# BT832A.net
KiCad netlist of a schematic drawn in EAGLE
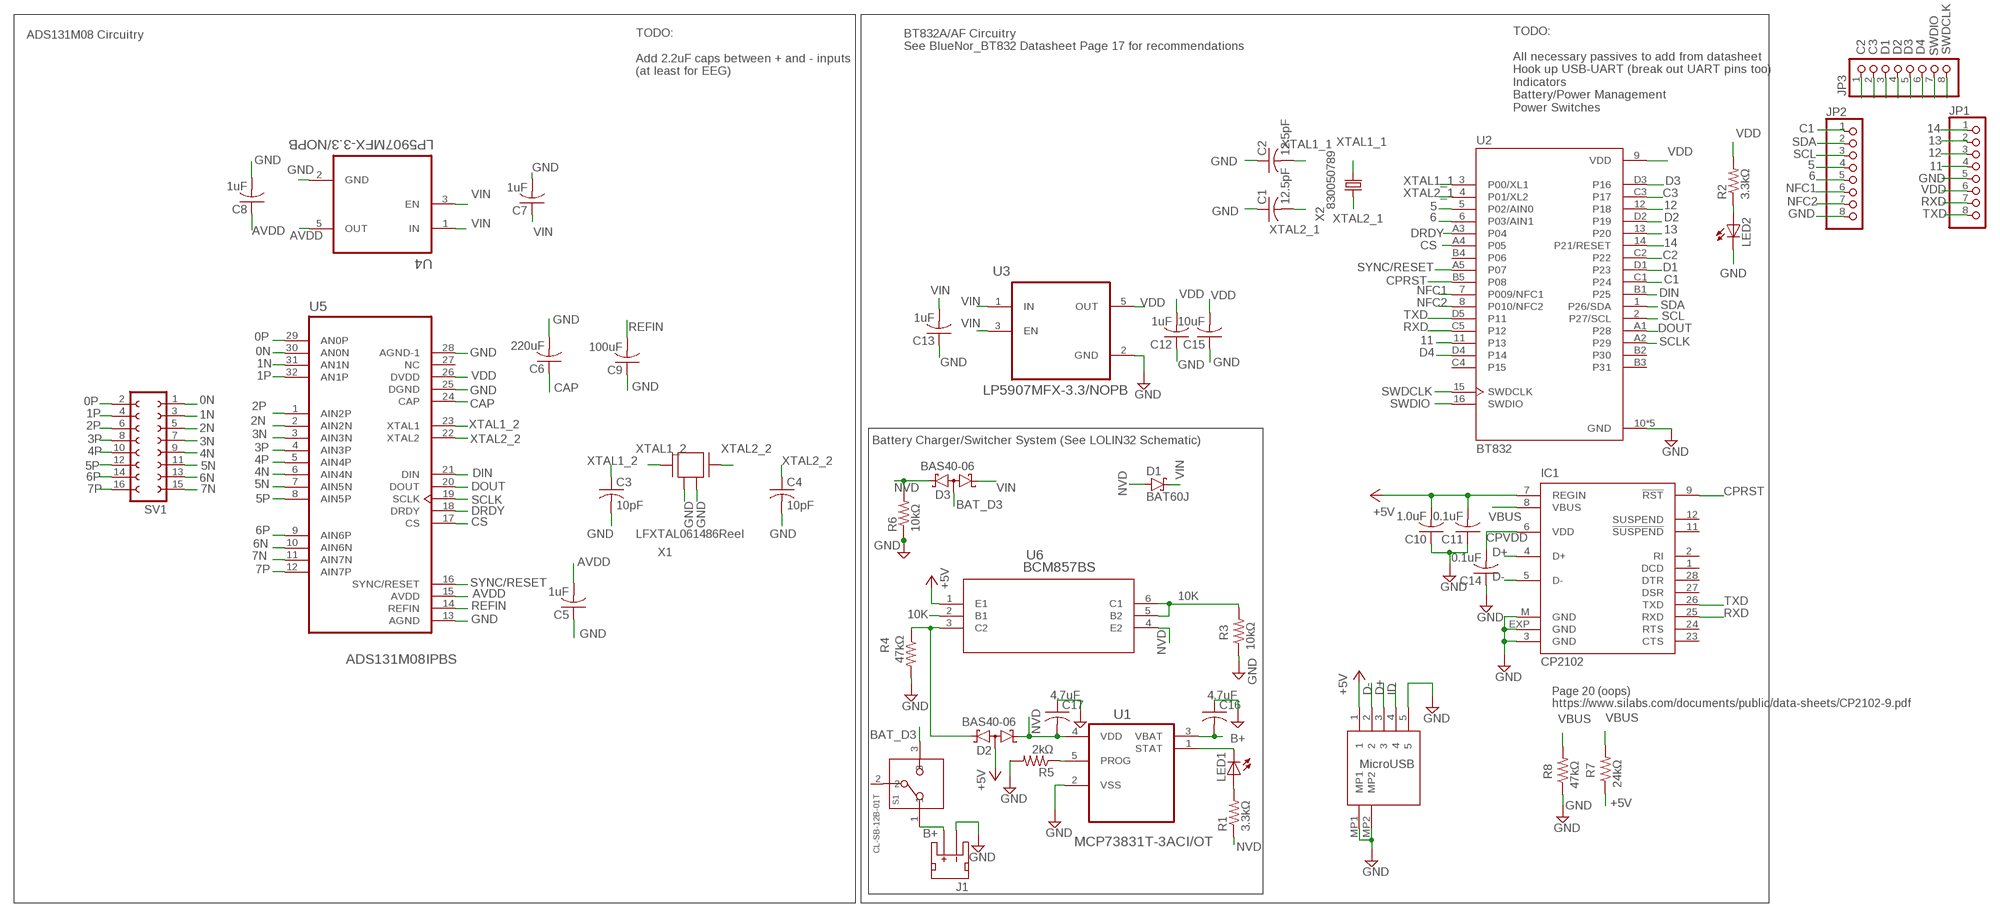
[diagram p0: schematic, sheet 1]

(export (version "E")
  (design (tool "Eeschema 10.0.6"))
  (components
    (comp (ref "C1")
      (value "12.5pF")
      (footprint "eagle-import:C0402")
      (libsource (lib "eagle-import") (part "adafruit_420_C-USC0402"))
    )
    (comp (ref "C2")
      (value "12.5pF")
      (footprint "eagle-import:C0402")
      (libsource (lib "eagle-import") (part "adafruit_420_C-USC0402"))
    )
    (comp (ref "C3")
      (value "10pF")
      (footprint "eagle-import:C0402")
      (libsource (lib "eagle-import") (part "adafruit_420_C-USC0402"))
    )
    (comp (ref "C4")
      (value "10pF")
      (footprint "eagle-import:C0402")
      (libsource (lib "eagle-import") (part "adafruit_420_C-USC0402"))
    )
    (comp (ref "C5")
      (value "1uF")
      (footprint "eagle-import:C0402")
      (libsource (lib "eagle-import") (part "C-USC0402"))
    )
    (comp (ref "C6")
      (value "220uF")
      (footprint "eagle-import:C0402")
      (libsource (lib "eagle-import") (part "C-USC0402"))
    )
    (comp (ref "C7")
      (value "1uF")
      (footprint "eagle-import:C0402")
      (libsource (lib "eagle-import") (part "C-USC0402"))
    )
    (comp (ref "C8")
      (value "1uF")
      (footprint "eagle-import:C0402")
      (libsource (lib "eagle-import") (part "C-USC0402"))
    )
    (comp (ref "C9")
      (value "100uF")
      (footprint "eagle-import:C0402")
      (libsource (lib "eagle-import") (part "C-USC0402"))
    )
    (comp (ref "C10")
      (value "1.0uF")
      (footprint "eagle-import:C0402")
      (libsource (lib "eagle-import") (part "adafruit_420_C-USC0402"))
    )
    (comp (ref "C11")
      (value "0.1uF")
      (footprint "eagle-import:C0402")
      (libsource (lib "eagle-import") (part "adafruit_420_C-USC0402"))
    )
    (comp (ref "C12")
      (value "1uF")
      (footprint "eagle-import:C0402")
      (libsource (lib "eagle-import") (part "C-USC0402"))
    )
    (comp (ref "C13")
      (value "1uF")
      (footprint "eagle-import:C0402")
      (libsource (lib "eagle-import") (part "C-USC0402"))
    )
    (comp (ref "C14")
      (value "0.1uF")
      (footprint "eagle-import:C0402")
      (libsource (lib "eagle-import") (part "adafruit_420_C-USC0402"))
    )
    (comp (ref "C15")
      (value "10uF")
      (footprint "eagle-import:C0402")
      (libsource (lib "eagle-import") (part "C-USC0402"))
    )
    (comp (ref "C16")
      (value "4.7uF")
      (footprint "eagle-import:C0402")
      (libsource (lib "eagle-import") (part "adafruit_420_C-USC0402"))
    )
    (comp (ref "C17")
      (value "4.7uF")
      (footprint "eagle-import:C0402")
      (libsource (lib "eagle-import") (part "adafruit_420_C-USC0402"))
    )
    (comp (ref "D1")
      (value "BAT60J")
      (footprint "eagle-import:SOD323_ST")
      (libsource (lib "eagle-import") (part "BAT60J"))
    )
    (comp (ref "D2")
      (value "BAS40-06")
      (footprint "eagle-import:SOT23")
      (libsource (lib "eagle-import") (part "BAS40-06"))
    )
    (comp (ref "D3")
      (value "BAS40-06")
      (footprint "eagle-import:SOT23")
      (libsource (lib "eagle-import") (part "BAS40-06"))
    )
    (comp (ref "IC1")
      (value "CP2102")
      (footprint "eagle-import:MLP28")
      (fields (field (name "MF") "FARNELL") (field (name "MPN") "CP2102-GM"))
      (libsource (lib "eagle-import") (part "CP2102"))
    )
    (comp (ref "J1")
      (value "JST_2MM_MALE")
      (footprint "eagle-import:JST-2-SMD")
      (libsource (lib "eagle-import") (part "JST_2MM_MALE"))
    )
    (comp (ref "JP1")
      (value "PINHD-1X8CLEANBIG")
      (footprint "eagle-import:1X08-CLEANBIG")
      (libsource (lib "eagle-import") (part "PINHD-1X8CLEANBIG"))
    )
    (comp (ref "JP2")
      (value "PINHD-1X8CLEANBIG")
      (footprint "eagle-import:1X08-CLEANBIG")
      (libsource (lib "eagle-import") (part "PINHD-1X8CLEANBIG"))
    )
    (comp (ref "JP3")
      (value "PINHD-1X8CLEANBIG")
      (footprint "eagle-import:1X08-CLEANBIG")
      (libsource (lib "eagle-import") (part "PINHD-1X8CLEANBIG"))
    )
    (comp (ref "LED1")
      (value "LEDCHIP-LED0603")
      (footprint "eagle-import:CHIP-LED0603")
      (libsource (lib "eagle-import") (part "LEDCHIP-LED0603"))
    )
    (comp (ref "LED2")
      (value "LEDCHIP-LED0603")
      (footprint "eagle-import:CHIP-LED0603")
      (libsource (lib "eagle-import") (part "LEDCHIP-LED0603"))
    )
    (comp (ref "R1")
      (value "3.3kΩ")
      (footprint "eagle-import:R0402")
      (libsource (lib "eagle-import") (part "R-US_R0402"))
    )
    (comp (ref "R2")
      (value "3.3kΩ")
      (footprint "eagle-import:R0402")
      (libsource (lib "eagle-import") (part "R-US_R0402"))
    )
    (comp (ref "R3")
      (value "10kΩ")
      (footprint "eagle-import:R0402")
      (libsource (lib "eagle-import") (part "R-US_R0402"))
    )
    (comp (ref "R4")
      (value "47kΩ")
      (footprint "eagle-import:R0402")
      (libsource (lib "eagle-import") (part "R-US_R0402"))
    )
    (comp (ref "R5")
      (value "2kΩ")
      (footprint "eagle-import:R0402")
      (libsource (lib "eagle-import") (part "R-US_R0402"))
    )
    (comp (ref "R6")
      (value "10kΩ")
      (footprint "eagle-import:R0402")
      (libsource (lib "eagle-import") (part "R-US_R0402"))
    )
    (comp (ref "R7")
      (value "24kΩ")
      (footprint "eagle-import:R0402")
      (libsource (lib "eagle-import") (part "R-US_R0402"))
    )
    (comp (ref "R8")
      (value "47kΩ")
      (footprint "eagle-import:R0402")
      (libsource (lib "eagle-import") (part "R-US_R0402"))
    )
    (comp (ref "S1")
      (value "CL-SB-12B-01T")
      (footprint "eagle-import:CL-SB-12B")
      (fields (field (name "MF") "Nidec Copal"))
      (libsource (lib "eagle-import") (part "CL-SB-12B-01T"))
    )
    (comp (ref "SV1")
      (value "FE08-2")
      (footprint "eagle-import:FE08-2")
      (libsource (lib "eagle-import") (part "FE08-2"))
    )
    (comp (ref "U$1")
      (value "DX4R005JJ2R1800")
      (footprint "eagle-import:DX4R005JJ2R1800")
      (fields (field (name "MF") "JAE Electronics"))
      (libsource (lib "eagle-import") (part "DX4R005JJ2R1800"))
    )
    (comp (ref "U1")
      (value "MCP73831T-3ACI/OT")
      (footprint "eagle-import:SOT95P270X145-5N")
      (fields (field (name "MF") "Microchip"))
      (libsource (lib "eagle-import") (part "MCP73831T-3ACI/OT"))
    )
    (comp (ref "U2")
      (value "BT832")
      (footprint "eagle-import:BLEMODULE_BT832")
      (fields (field (name "MF") "Fanstel Corp."))
      (libsource (lib "eagle-import") (part "BT832"))
    )
    (comp (ref "U3")
      (value "LP5907MFX-3.3/NOPB")
      (footprint "eagle-import:SOT95P280X145-5N")
      (fields (field (name "MF") "Texas Instruments"))
      (libsource (lib "eagle-import") (part "LP5907MFX-3.3/NOPB"))
    )
    (comp (ref "U4")
      (value "LP5907MFX-3.3/NOPB")
      (footprint "eagle-import:SOT95P280X145-5N")
      (fields (field (name "MF") "Texas Instruments"))
      (libsource (lib "eagle-import") (part "LP5907MFX-3.3/NOPB"))
    )
    (comp (ref "U5")
      (value "ADS131M08IPBS")
      (footprint "eagle-import:QFP50P700X700X120-32N")
      (fields (field (name "MF") "Texas Instruments"))
      (libsource (lib "eagle-import") (part "ADS131M08IPBS"))
    )
    (comp (ref "U6")
      (value "BCM857BS")
      (footprint "eagle-import:SOT363_NEX")
      (fields (field (name "COPYRIGHT") "Copyright (C) 2016 Accelerated Designs. All rights reserved"))
      (libsource (lib "eagle-import") (part "BCM857BS"))
    )
    (comp (ref "X1")
      (value "ABM3B-8.000MHZ-B2-T")
      (footprint "eagle-import:ABM3B-8.000MHZ-B2-T")
      (fields
        (field (name "DIGIKEY_PART_NUMBER") "535-9720-2-ND")
        (field (name "MANUFACTURER") "Abracon LLC")
        (field (name "CREATED_BY") "PCBLayout.com")
      )
      (libsource (lib "eagle-import") (part "ABM3B-8.000MHZ-B2-T"))
    )
    (comp (ref "X2")
      (value "FC-12M")
      (footprint "eagle-import:FC-12M")
      (libsource (lib "eagle-import") (part "FC-12M"))
    )
  )
  (nets
    (net (code "1") (name "+5V") (class "Default")
      (node (ref "C10") (pin "2") (pinfunction "2_2") (pintype "passive"))
      (node (ref "C11") (pin "2") (pinfunction "2_2") (pintype "passive"))
      (node (ref "D2") (pin "3") (pinfunction "AA_3") (pintype "passive"))
      (node (ref "IC1") (pin "7") (pinfunction "REGIN_7") (pintype "passive"))
      (node (ref "R7") (pin "1") (pinfunction "1_1") (pintype "passive"))
      (node (ref "U$1") (pin "1") (pinfunction "1_1") (pintype "bidirectional"))
      (node (ref "U6") (pin "1") (pinfunction "E1_1") (pintype "passive"))
    )
    (net (code "2") (name "0N") (class "Default")
      (node (ref "SV1") (pin "1") (pinfunction "1_1") (pintype "passive"))
      (node (ref "U5") (pin "30") (pinfunction "AN0N_30") (pintype "bidirectional"))
    )
    (net (code "3") (name "0P") (class "Default")
      (node (ref "SV1") (pin "2") (pinfunction "2_2") (pintype "passive"))
      (node (ref "U5") (pin "29") (pinfunction "AN0P_29") (pintype "bidirectional"))
    )
    (net (code "4") (name "1N") (class "Default")
      (node (ref "SV1") (pin "3") (pinfunction "3_3") (pintype "passive"))
      (node (ref "U5") (pin "31") (pinfunction "AN1N_31") (pintype "bidirectional"))
    )
    (net (code "5") (name "1P") (class "Default")
      (node (ref "SV1") (pin "4") (pinfunction "4_4") (pintype "passive"))
      (node (ref "U5") (pin "32") (pinfunction "AN1P_32") (pintype "bidirectional"))
    )
    (net (code "6") (name "2N") (class "Default")
      (node (ref "SV1") (pin "5") (pinfunction "5_5") (pintype "passive"))
      (node (ref "U5") (pin "2") (pinfunction "AIN2N_2") (pintype "input"))
    )
    (net (code "7") (name "2P") (class "Default")
      (node (ref "SV1") (pin "6") (pinfunction "6_6") (pintype "passive"))
      (node (ref "U5") (pin "1") (pinfunction "AIN2P_1") (pintype "input"))
    )
    (net (code "8") (name "3N") (class "Default")
      (node (ref "SV1") (pin "7") (pinfunction "7_7") (pintype "passive"))
      (node (ref "U5") (pin "3") (pinfunction "AIN3N_3") (pintype "input"))
    )
    (net (code "9") (name "3P") (class "Default")
      (node (ref "SV1") (pin "8") (pinfunction "8_8") (pintype "passive"))
      (node (ref "U5") (pin "4") (pinfunction "AIN3P_4") (pintype "input"))
    )
    (net (code "10") (name "4N") (class "Default")
      (node (ref "SV1") (pin "9") (pinfunction "9_9") (pintype "passive"))
      (node (ref "U5") (pin "6") (pinfunction "AIN4N_6") (pintype "input"))
    )
    (net (code "11") (name "4P") (class "Default")
      (node (ref "SV1") (pin "10") (pinfunction "10_10") (pintype "passive"))
      (node (ref "U5") (pin "5") (pinfunction "AIN4P_5") (pintype "input"))
    )
    (net (code "12") (name "5") (class "Default")
      (node (ref "JP2") (pin "4") (pinfunction "4_4") (pintype "passive"))
      (node (ref "U2") (pin "5") (pinfunction "P02/AIN0_5") (pintype "bidirectional"))
    )
    (net (code "13") (name "5N") (class "Default")
      (node (ref "SV1") (pin "11") (pinfunction "11_11") (pintype "passive"))
      (node (ref "U5") (pin "7") (pinfunction "AIN5N_7") (pintype "input"))
    )
    (net (code "14") (name "5P") (class "Default")
      (node (ref "SV1") (pin "12") (pinfunction "12_12") (pintype "passive"))
      (node (ref "U5") (pin "8") (pinfunction "AIN5P_8") (pintype "input"))
    )
    (net (code "15") (name "6") (class "Default")
      (node (ref "JP2") (pin "5") (pinfunction "5_5") (pintype "passive"))
      (node (ref "U2") (pin "6") (pinfunction "P03/AIN1_6") (pintype "bidirectional"))
    )
    (net (code "16") (name "6N") (class "Default")
      (node (ref "SV1") (pin "13") (pinfunction "13_13") (pintype "passive"))
      (node (ref "U5") (pin "10") (pinfunction "AIN6N_10") (pintype "input"))
    )
    (net (code "17") (name "6P") (class "Default")
      (node (ref "SV1") (pin "14") (pinfunction "14_14") (pintype "passive"))
      (node (ref "U5") (pin "9") (pinfunction "AIN6P_9") (pintype "input"))
    )
    (net (code "18") (name "7N") (class "Default")
      (node (ref "SV1") (pin "15") (pinfunction "15_15") (pintype "passive"))
      (node (ref "U5") (pin "11") (pinfunction "AIN7N_11") (pintype "input"))
    )
    (net (code "19") (name "7P") (class "Default")
      (node (ref "SV1") (pin "16") (pinfunction "16_16") (pintype "passive"))
      (node (ref "U5") (pin "12") (pinfunction "AIN7P_12") (pintype "input"))
    )
    (net (code "20") (name "10K") (class "Default")
      (node (ref "R3") (pin "2") (pinfunction "2_2") (pintype "passive"))
      (node (ref "U6") (pin "2") (pinfunction "B1_2") (pintype "passive"))
      (node (ref "U6") (pin "5") (pinfunction "B2_5") (pintype "passive"))
      (node (ref "U6") (pin "6") (pinfunction "C1_6") (pintype "passive"))
    )
    (net (code "21") (name "11") (class "Default")
      (node (ref "JP1") (pin "4") (pinfunction "4_4") (pintype "passive"))
      (node (ref "U2") (pin "11") (pinfunction "P13_11") (pintype "bidirectional"))
    )
    (net (code "22") (name "12") (class "Default")
      (node (ref "JP1") (pin "3") (pinfunction "3_3") (pintype "passive"))
      (node (ref "U2") (pin "12") (pinfunction "P18_12") (pintype "bidirectional"))
    )
    (net (code "23") (name "13") (class "Default")
      (node (ref "JP1") (pin "2") (pinfunction "2_2") (pintype "passive"))
      (node (ref "U2") (pin "13") (pinfunction "P20_13") (pintype "bidirectional"))
    )
    (net (code "24") (name "14") (class "Default")
      (node (ref "JP1") (pin "1") (pinfunction "1_1") (pintype "passive"))
      (node (ref "U2") (pin "14") (pinfunction "P21/RESET_14") (pintype "bidirectional"))
    )
    (net (code "25") (name "AVDD") (class "Default")
      (node (ref "C5") (pin "2") (pinfunction "2_2") (pintype "passive"))
      (node (ref "C8") (pin "1") (pinfunction "1_1") (pintype "passive"))
      (node (ref "U4") (pin "5") (pinfunction "OUT_5") (pintype "output"))
      (node (ref "U5") (pin "15") (pinfunction "AVDD_15") (pintype "power_in"))
    )
    (net (code "26") (name "B+") (class "Default")
      (node (ref "C16") (pin "2") (pinfunction "2_2") (pintype "passive"))
      (node (ref "J1") (pin "2") (pinfunction "+_2") (pintype "bidirectional"))
      (node (ref "S1") (pin "1") (pinfunction "1_1") (pintype "bidirectional"))
      (node (ref "U1") (pin "3") (pinfunction "VBAT_3") (pintype "power_in"))
    )
    (net (code "27") (name "BAT_D3") (class "Default")
      (node (ref "D3") (pin "3") (pinfunction "AA_3") (pintype "passive"))
      (node (ref "S1") (pin "3") (pinfunction "3_3") (pintype "bidirectional"))
    )
    (net (code "28") (name "C1") (class "Default")
      (node (ref "JP2") (pin "1") (pinfunction "1_1") (pintype "passive"))
      (node (ref "U2") (pin "C1") (pinfunction "P24_C1") (pintype "bidirectional"))
    )
    (net (code "29") (name "C2") (class "Default")
      (node (ref "JP3") (pin "1") (pinfunction "1_1") (pintype "passive"))
      (node (ref "U2") (pin "C2") (pinfunction "P22_C2") (pintype "bidirectional"))
    )
    (net (code "30") (name "C3") (class "Default")
      (node (ref "JP3") (pin "2") (pinfunction "2_2") (pintype "passive"))
      (node (ref "U2") (pin "C3") (pinfunction "P17_C3") (pintype "bidirectional"))
    )
    (net (code "31") (name "CAP") (class "Default")
      (node (ref "C6") (pin "1") (pinfunction "1_1") (pintype "passive"))
      (node (ref "U5") (pin "24") (pinfunction "CAP_24") (pintype "bidirectional"))
    )
    (net (code "32") (name "CPRST") (class "Default")
      (node (ref "IC1") (pin "9") (pinfunction "~{RST}_9") (pintype "bidirectional"))
      (node (ref "U2") (pin "B5") (pinfunction "P08_B5") (pintype "bidirectional"))
    )
    (net (code "33") (name "CPVDD") (class "Default")
      (node (ref "C14") (pin "2") (pinfunction "2_2") (pintype "passive"))
      (node (ref "IC1") (pin "6") (pinfunction "VDD_6") (pintype "power_in"))
    )
    (net (code "34") (name "CS") (class "Default")
      (node (ref "U2") (pin "A4") (pinfunction "P05_A4") (pintype "bidirectional"))
      (node (ref "U5") (pin "17") (pinfunction "CS_17") (pintype "bidirectional"))
    )
    (net (code "35") (name "D+") (class "Default")
      (node (ref "IC1") (pin "4") (pinfunction "D+_4") (pintype "bidirectional"))
      (node (ref "U$1") (pin "3") (pinfunction "3_3") (pintype "bidirectional"))
    )
    (net (code "36") (name "D-") (class "Default")
      (node (ref "IC1") (pin "5") (pinfunction "D-_5") (pintype "bidirectional"))
      (node (ref "U$1") (pin "2") (pinfunction "2_2") (pintype "bidirectional"))
    )
    (net (code "37") (name "D1") (class "Default")
      (node (ref "JP3") (pin "3") (pinfunction "3_3") (pintype "passive"))
      (node (ref "U2") (pin "D1") (pinfunction "P23_D1") (pintype "bidirectional"))
    )
    (net (code "38") (name "D2") (class "Default")
      (node (ref "JP3") (pin "4") (pinfunction "4_4") (pintype "passive"))
      (node (ref "U2") (pin "D2") (pinfunction "P19_D2") (pintype "bidirectional"))
    )
    (net (code "39") (name "D3") (class "Default")
      (node (ref "JP3") (pin "5") (pinfunction "5_5") (pintype "passive"))
      (node (ref "U2") (pin "D3") (pinfunction "P16_D3") (pintype "bidirectional"))
    )
    (net (code "40") (name "D4") (class "Default")
      (node (ref "JP3") (pin "6") (pinfunction "6_6") (pintype "passive"))
      (node (ref "U2") (pin "D4") (pinfunction "P14_D4") (pintype "bidirectional"))
    )
    (net (code "41") (name "DIN") (class "Default")
      (node (ref "U2") (pin "B1") (pinfunction "P25_B1") (pintype "bidirectional"))
      (node (ref "U5") (pin "21") (pinfunction "DIN_21") (pintype "input"))
    )
    (net (code "42") (name "DOUT") (class "Default")
      (node (ref "U2") (pin "A1") (pinfunction "P28_A1") (pintype "bidirectional"))
      (node (ref "U5") (pin "20") (pinfunction "DOUT_20") (pintype "output"))
    )
    (net (code "43") (name "DRDY") (class "Default")
      (node (ref "U2") (pin "A3") (pinfunction "P04_A3") (pintype "bidirectional"))
      (node (ref "U5") (pin "18") (pinfunction "DRDY_18") (pintype "output"))
    )
    (net (code "44") (name "GND") (class "Default")
      (node (ref "C1") (pin "1") (pinfunction "1_1") (pintype "passive"))
      (node (ref "C10") (pin "1") (pinfunction "1_1") (pintype "passive"))
      (node (ref "C11") (pin "1") (pinfunction "1_1") (pintype "passive"))
      (node (ref "C12") (pin "1") (pinfunction "1_1") (pintype "passive"))
      (node (ref "C13") (pin "1") (pinfunction "1_1") (pintype "passive"))
      (node (ref "C14") (pin "1") (pinfunction "1_1") (pintype "passive"))
      (node (ref "C15") (pin "1") (pinfunction "1_1") (pintype "passive"))
      (node (ref "C16") (pin "1") (pinfunction "1_1") (pintype "passive"))
      (node (ref "C17") (pin "1") (pinfunction "1_1") (pintype "passive"))
      (node (ref "C2") (pin "1") (pinfunction "1_1") (pintype "passive"))
      (node (ref "C3") (pin "2") (pinfunction "2_2") (pintype "passive"))
      (node (ref "C4") (pin "2") (pinfunction "2_2") (pintype "passive"))
      (node (ref "C5") (pin "1") (pinfunction "1_1") (pintype "passive"))
      (node (ref "C6") (pin "2") (pinfunction "2_2") (pintype "passive"))
      (node (ref "C7") (pin "2") (pinfunction "2_2") (pintype "passive"))
      (node (ref "C8") (pin "2") (pinfunction "2_2") (pintype "passive"))
      (node (ref "C9") (pin "1") (pinfunction "1_1") (pintype "passive"))
      (node (ref "IC1") (pin "3") (pinfunction "GND_3") (pintype "power_in"))
      (node (ref "IC1") (pin "EXP") (pinfunction "GND_EXP") (pintype "power_in"))
      (node (ref "IC1") (pin "M") (pinfunction "GND_M") (pintype "power_in"))
      (node (ref "J1") (pin "1") (pinfunction "-_1") (pintype "bidirectional"))
      (node (ref "JP1") (pin "5") (pinfunction "5_5") (pintype "passive"))
      (node (ref "JP2") (pin "8") (pinfunction "8_8") (pintype "passive"))
      (node (ref "LED2") (pin "C") (pinfunction "C_C") (pintype "passive"))
      (node (ref "R3") (pin "1") (pinfunction "1_1") (pintype "passive"))
      (node (ref "R4") (pin "2") (pinfunction "2_2") (pintype "passive"))
      (node (ref "R5") (pin "2") (pinfunction "2_2") (pintype "passive"))
      (node (ref "R6") (pin "1") (pinfunction "1_1") (pintype "passive"))
      (node (ref "R8") (pin "1") (pinfunction "1_1") (pintype "passive"))
      (node (ref "U$1") (pin "5") (pinfunction "5_5") (pintype "bidirectional"))
      (node (ref "U$1") (pin "MP1") (pinfunction "MP1_MP1") (pintype "bidirectional"))
      (node (ref "U$1") (pin "MP2") (pinfunction "MP2_MP2") (pintype "bidirectional"))
      (node (ref "U1") (pin "2") (pinfunction "VSS_2") (pintype "power_in"))
      (node (ref "U2") (pin "10") (pinfunction "GND_10") (pintype "power_in"))
      (node (ref "U2") (pin "A0") (pinfunction "GND_A0") (pintype "power_in"))
      (node (ref "U2") (pin "B0") (pinfunction "GND_B0") (pintype "power_in"))
      (node (ref "U2") (pin "C0") (pinfunction "GND_C0") (pintype "power_in"))
      (node (ref "U2") (pin "D0") (pinfunction "GND_D0") (pintype "power_in"))
      (node (ref "U3") (pin "2") (pinfunction "GND_2") (pintype "power_in"))
      (node (ref "U4") (pin "2") (pinfunction "GND_2") (pintype "power_in"))
      (node (ref "U5") (pin "13") (pinfunction "AGND_13") (pintype "power_in"))
      (node (ref "U5") (pin "25") (pinfunction "DGND_25") (pintype "power_in"))
      (node (ref "U5") (pin "28") (pinfunction "AGND-1_28") (pintype "power_in"))
      (node (ref "X1") (pin "2") (pinfunction "2_2") (pintype "passive"))
      (node (ref "X1") (pin "4") (pinfunction "4_4") (pintype "passive"))
    )
    (net (code "45") (name "ID") (class "Default")
      (node (ref "U$1") (pin "4") (pinfunction "4_4") (pintype "bidirectional"))
    )
    (net (code "46") (name "NFC1") (class "Default")
      (node (ref "JP2") (pin "6") (pinfunction "6_6") (pintype "passive"))
      (node (ref "U2") (pin "7") (pinfunction "P009/NFC1_7") (pintype "bidirectional"))
    )
    (net (code "47") (name "NFC2") (class "Default")
      (node (ref "JP2") (pin "7") (pinfunction "7_7") (pintype "passive"))
      (node (ref "U2") (pin "8") (pinfunction "P010/NFC2_8") (pintype "bidirectional"))
    )
    (net (code "48") (name "NVD") (class "Default")
      (node (ref "C17") (pin "2") (pinfunction "2_2") (pintype "passive"))
      (node (ref "D1") (pin "A") (pinfunction "A_A") (pintype "passive"))
      (node (ref "D2") (pin "1") (pinfunction "K1_1") (pintype "passive"))
      (node (ref "D3") (pin "2") (pinfunction "K2_2") (pintype "passive"))
      (node (ref "R1") (pin "1") (pinfunction "1_1") (pintype "passive"))
      (node (ref "R6") (pin "2") (pinfunction "2_2") (pintype "passive"))
      (node (ref "U1") (pin "4") (pinfunction "VDD_4") (pintype "power_in"))
      (node (ref "U6") (pin "4") (pinfunction "E2_4") (pintype "passive"))
    )
    (net (code "49") (name "Net-(D2-K2)") (class "Default")
      (node (ref "D2") (pin "2") (pinfunction "K2_2") (pintype "passive"))
      (node (ref "R4") (pin "1") (pinfunction "1_1") (pintype "passive"))
      (node (ref "U6") (pin "3") (pinfunction "C2_3") (pintype "passive"))
    )
    (net (code "50") (name "Net-(LED1-PadA)") (class "Default")
      (node (ref "LED1") (pin "A") (pinfunction "A_A") (pintype "passive"))
      (node (ref "R1") (pin "2") (pinfunction "2_2") (pintype "passive"))
    )
    (net (code "51") (name "Net-(LED2-PadA)") (class "Default")
      (node (ref "LED2") (pin "A") (pinfunction "A_A") (pintype "passive"))
      (node (ref "R2") (pin "1") (pinfunction "1_1") (pintype "passive"))
    )
    (net (code "52") (name "Net-(U1-PROG)") (class "Default")
      (node (ref "R5") (pin "1") (pinfunction "1_1") (pintype "passive"))
      (node (ref "U1") (pin "5") (pinfunction "PROG_5") (pintype "input"))
    )
    (net (code "53") (name "Net-(U1-STAT)") (class "Default")
      (node (ref "LED1") (pin "C") (pinfunction "C_C") (pintype "passive"))
      (node (ref "U1") (pin "1") (pinfunction "STAT_1") (pintype "output"))
    )
    (net (code "54") (name "REFIN") (class "Default")
      (node (ref "C9") (pin "2") (pinfunction "2_2") (pintype "passive"))
      (node (ref "U5") (pin "14") (pinfunction "REFIN_14") (pintype "input"))
    )
    (net (code "55") (name "RXD") (class "Default")
      (node (ref "IC1") (pin "25") (pinfunction "RXD_25") (pintype "input"))
      (node (ref "JP1") (pin "7") (pinfunction "7_7") (pintype "passive"))
      (node (ref "U2") (pin "C5") (pinfunction "P12_C5") (pintype "bidirectional"))
    )
    (net (code "56") (name "SCL") (class "Default")
      (node (ref "JP2") (pin "3") (pinfunction "3_3") (pintype "passive"))
      (node (ref "U2") (pin "2") (pinfunction "P27/SCL_2") (pintype "bidirectional"))
    )
    (net (code "57") (name "SCLK") (class "Default")
      (node (ref "U2") (pin "A2") (pinfunction "P29_A2") (pintype "bidirectional"))
      (node (ref "U5") (pin "19") (pinfunction "SCLK_19") (pintype "input"))
    )
    (net (code "58") (name "SDA") (class "Default")
      (node (ref "JP2") (pin "2") (pinfunction "2_2") (pintype "passive"))
      (node (ref "U2") (pin "1") (pinfunction "P26/SDA_1") (pintype "bidirectional"))
    )
    (net (code "59") (name "SWDCLK") (class "Default")
      (node (ref "JP3") (pin "8") (pinfunction "8_8") (pintype "passive"))
      (node (ref "U2") (pin "15") (pinfunction "SWDCLK_15") (pintype "input"))
    )
    (net (code "60") (name "SWDIO") (class "Default")
      (node (ref "JP3") (pin "7") (pinfunction "7_7") (pintype "passive"))
      (node (ref "U2") (pin "16") (pinfunction "SWDIO_16") (pintype "bidirectional"))
    )
    (net (code "61") (name "SYNC{slash}RESET") (class "Default")
      (node (ref "U2") (pin "A5") (pinfunction "P07_A5") (pintype "bidirectional"))
      (node (ref "U5") (pin "16") (pinfunction "SYNC/RESET_16") (pintype "bidirectional"))
    )
    (net (code "62") (name "TXD") (class "Default")
      (node (ref "IC1") (pin "26") (pinfunction "TXD_26") (pintype "output"))
      (node (ref "JP1") (pin "8") (pinfunction "8_8") (pintype "passive"))
      (node (ref "U2") (pin "D5") (pinfunction "P11_D5") (pintype "bidirectional"))
    )
    (net (code "63") (name "VBUS") (class "Default")
      (node (ref "IC1") (pin "8") (pinfunction "VBUS_8") (pintype "input"))
      (node (ref "R7") (pin "2") (pinfunction "2_2") (pintype "passive"))
      (node (ref "R8") (pin "2") (pinfunction "2_2") (pintype "passive"))
    )
    (net (code "64") (name "VDD") (class "Default")
      (node (ref "C12") (pin "2") (pinfunction "2_2") (pintype "passive"))
      (node (ref "C15") (pin "2") (pinfunction "2_2") (pintype "passive"))
      (node (ref "JP1") (pin "6") (pinfunction "6_6") (pintype "passive"))
      (node (ref "R2") (pin "2") (pinfunction "2_2") (pintype "passive"))
      (node (ref "U2") (pin "9") (pinfunction "VDD_9") (pintype "power_in"))
      (node (ref "U3") (pin "5") (pinfunction "OUT_5") (pintype "output"))
      (node (ref "U5") (pin "26") (pinfunction "DVDD_26") (pintype "power_in"))
    )
    (net (code "65") (name "VIN") (class "Default")
      (node (ref "C13") (pin "2") (pinfunction "2_2") (pintype "passive"))
      (node (ref "C7") (pin "1") (pinfunction "1_1") (pintype "passive"))
      (node (ref "D1") (pin "C") (pinfunction "C_C") (pintype "passive"))
      (node (ref "D3") (pin "1") (pinfunction "K1_1") (pintype "passive"))
      (node (ref "U3") (pin "1") (pinfunction "IN_1") (pintype "input"))
      (node (ref "U3") (pin "3") (pinfunction "EN_3") (pintype "input"))
      (node (ref "U4") (pin "1") (pinfunction "IN_1") (pintype "input"))
      (node (ref "U4") (pin "3") (pinfunction "EN_3") (pintype "input"))
    )
    (net (code "66") (name "XTAL1_1") (class "Default")
      (node (ref "C2") (pin "2") (pinfunction "2_2") (pintype "passive"))
      (node (ref "U2") (pin "3") (pinfunction "P00/XL1_3") (pintype "bidirectional"))
      (node (ref "X2") (pin "2") (pinfunction "2_2") (pintype "passive"))
    )
    (net (code "67") (name "XTAL1_2") (class "Default")
      (node (ref "C3") (pin "1") (pinfunction "1_1") (pintype "passive"))
      (node (ref "U5") (pin "23") (pinfunction "XTAL1_23") (pintype "bidirectional"))
      (node (ref "X1") (pin "1") (pinfunction "1_1") (pintype "passive"))
    )
    (net (code "68") (name "XTAL2_1") (class "Default")
      (node (ref "C1") (pin "2") (pinfunction "2_2") (pintype "passive"))
      (node (ref "U2") (pin "4") (pinfunction "P01/XL2_4") (pintype "bidirectional"))
      (node (ref "X2") (pin "1") (pinfunction "1_1") (pintype "passive"))
    )
    (net (code "69") (name "XTAL2_2") (class "Default")
      (node (ref "C4") (pin "1") (pinfunction "1_1") (pintype "passive"))
      (node (ref "U5") (pin "22") (pinfunction "XTAL2_22") (pintype "bidirectional"))
      (node (ref "X1") (pin "3") (pinfunction "3_3") (pintype "passive"))
    )
    (net (code "70") (name "unconnected-(IC1-CTS-Pad23)") (class "Default")
      (node (ref "IC1") (pin "23") (pinfunction "CTS_23") (pintype "input"))
    )
    (net (code "71") (name "unconnected-(IC1-DCD-Pad1)") (class "Default")
      (node (ref "IC1") (pin "1") (pinfunction "DCD_1") (pintype "input"))
    )
    (net (code "72") (name "unconnected-(IC1-DSR-Pad27)") (class "Default")
      (node (ref "IC1") (pin "27") (pinfunction "DSR_27") (pintype "input"))
    )
    (net (code "73") (name "unconnected-(IC1-DTR-Pad28)") (class "Default")
      (node (ref "IC1") (pin "28") (pinfunction "DTR_28") (pintype "output"))
    )
    (net (code "74") (name "unconnected-(IC1-RI-Pad2)") (class "Default")
      (node (ref "IC1") (pin "2") (pinfunction "RI_2") (pintype "input"))
    )
    (net (code "75") (name "unconnected-(IC1-RTS-Pad24)") (class "Default")
      (node (ref "IC1") (pin "24") (pinfunction "RTS_24") (pintype "output"))
    )
    (net (code "76") (name "unconnected-(IC1-SUSPEND-Pad12)") (class "Default")
      (node (ref "IC1") (pin "12") (pinfunction "SUSPEND_12") (pintype "output"))
    )
    (net (code "77") (name "unconnected-(IC1-~{SUSPEND}-Pad11)") (class "Default")
      (node (ref "IC1") (pin "11") (pinfunction "~{SUSPEND}_11") (pintype "output"))
    )
    (net (code "78") (name "unconnected-(J1-PAD1-PadNC1)") (class "Default")
      (node (ref "J1") (pin "NC1") (pinfunction "PAD1_NC1") (pintype "bidirectional"))
    )
    (net (code "79") (name "unconnected-(J1-PAD2-PadNC2)") (class "Default")
      (node (ref "J1") (pin "NC2") (pinfunction "PAD2_NC2") (pintype "bidirectional"))
    )
    (net (code "80") (name "unconnected-(S1-Pad2)") (class "Default")
      (node (ref "S1") (pin "2") (pinfunction "2_2") (pintype "bidirectional"))
    )
    (net (code "81") (name "unconnected-(U2-P06-PadB4)") (class "Default")
      (node (ref "U2") (pin "B4") (pinfunction "P06_B4") (pintype "bidirectional"))
    )
    (net (code "82") (name "unconnected-(U2-P15-PadC4)") (class "Default")
      (node (ref "U2") (pin "C4") (pinfunction "P15_C4") (pintype "bidirectional"))
    )
    (net (code "83") (name "unconnected-(U2-P30-PadB2)") (class "Default")
      (node (ref "U2") (pin "B2") (pinfunction "P30_B2") (pintype "bidirectional"))
    )
    (net (code "84") (name "unconnected-(U2-P31-PadB3)") (class "Default")
      (node (ref "U2") (pin "B3") (pinfunction "P31_B3") (pintype "bidirectional"))
    )
    (net (code "85") (name "unconnected-(U5-NC-Pad27)") (class "Default")
      (node (ref "U5") (pin "27") (pinfunction "NC_27") (pintype "bidirectional"))
    )
  )
)
